# nvs_gps.net
KiCad netlist of a schematic drawn in EAGLE
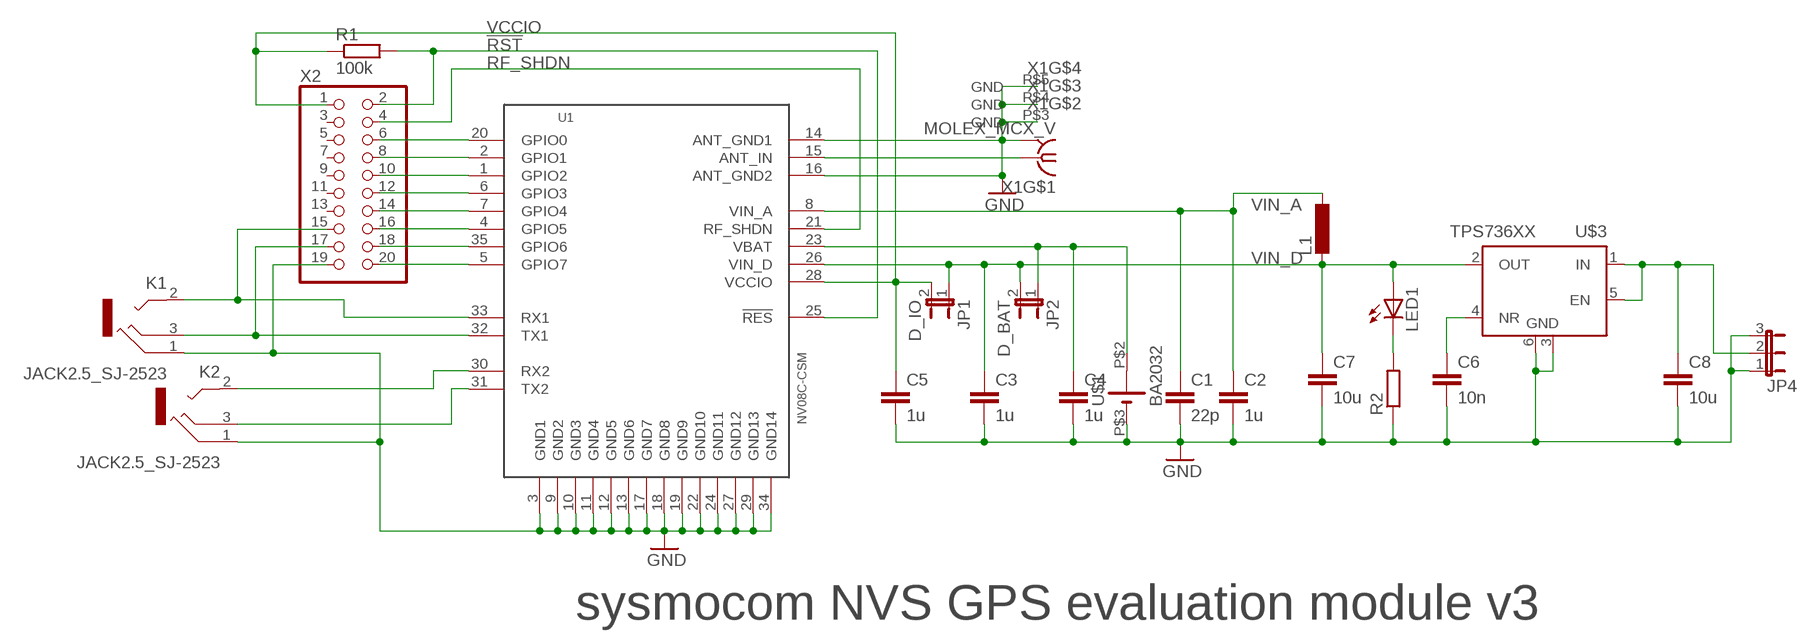
[diagram p0: schematic, sheet 1]

(export (version "E")
  (design (tool "Eeschema 10.0.6"))
  (components
    (comp (ref "C1")
      (value "22p")
      (footprint "eagle-import:C0402K")
      (libsource (lib "eagle-import") (part "C-EUC0402K"))
    )
    (comp (ref "C2")
      (value "1u")
      (footprint "eagle-import:C0603")
      (libsource (lib "eagle-import") (part "C-EUC0603"))
    )
    (comp (ref "C3")
      (value "1u")
      (footprint "eagle-import:C0603")
      (libsource (lib "eagle-import") (part "C-EUC0603"))
    )
    (comp (ref "C4")
      (value "1u")
      (footprint "eagle-import:C0603")
      (libsource (lib "eagle-import") (part "C-EUC0603"))
    )
    (comp (ref "C5")
      (value "1u")
      (footprint "eagle-import:C0603")
      (libsource (lib "eagle-import") (part "C-EUC0603"))
    )
    (comp (ref "C6")
      (value "10n")
      (footprint "eagle-import:C0603")
      (libsource (lib "eagle-import") (part "C-EUC0603"))
    )
    (comp (ref "C7")
      (value "10u")
      (footprint "eagle-import:C0603")
      (libsource (lib "eagle-import") (part "C-EUC0603"))
    )
    (comp (ref "C8")
      (value "10u")
      (footprint "eagle-import:C0603")
      (libsource (lib "eagle-import") (part "C-EUC0603"))
    )
    (comp (ref "JP1")
      (value "D_IO")
      (footprint "eagle-import:JP1")
      (libsource (lib "eagle-import") (part "JP1E"))
    )
    (comp (ref "JP2")
      (value "D_BAT")
      (footprint "eagle-import:JP1")
      (libsource (lib "eagle-import") (part "JP1E"))
    )
    (comp (ref "JP4")
      (value "JP2E")
      (footprint "eagle-import:JP2")
      (libsource (lib "eagle-import") (part "JP2E"))
    )
    (comp (ref "K1")
      (value "JACK2.5_SJ-2523")
      (footprint "eagle-import:JACK2.5_SJ-2523")
      (libsource (lib "eagle-import") (part "JACK2.5_SJ-2523"))
    )
    (comp (ref "K2")
      (value "JACK2.5_SJ-2523")
      (footprint "eagle-import:JACK2.5_SJ-2523")
      (libsource (lib "eagle-import") (part "JACK2.5_SJ-2523"))
    )
    (comp (ref "L1")
      (value "L-EU0603")
      (footprint "eagle-import:0603")
      (libsource (lib "eagle-import") (part "L-EU0603"))
    )
    (comp (ref "LED1")
      (value "LED0603")
      (footprint "eagle-import:LED-0603")
      (libsource (lib "eagle-import") (part "LED0603"))
    )
    (comp (ref "R1")
      (value "100k")
      (footprint "eagle-import:R0603")
      (libsource (lib "eagle-import") (part "R-EU_R0603"))
    )
    (comp (ref "R2")
      (value "R-EU_R0603")
      (footprint "eagle-import:R0603")
      (libsource (lib "eagle-import") (part "R-EU_R0603"))
    )
    (comp (ref "U$1")
      (value "BA2032")
      (footprint "eagle-import:BA2023-ND")
      (libsource (lib "eagle-import") (part "BA2032"))
    )
    (comp (ref "U$3")
      (value "TPS736XX")
      (footprint "eagle-import:SOT223-6")
      (libsource (lib "eagle-import") (part "TPS736XX"))
    )
    (comp (ref "U1")
      (value "NV08C-CSM")
      (footprint "eagle-import:NV08C-CSM")
      (libsource (lib "eagle-import") (part "NV08C-CSM"))
    )
    (comp (ref "X1")
      (value "MOLEX_MCX_V")
      (footprint "eagle-import:MOLEX_MCX_V")
      (libsource (lib "eagle-import") (part "MOLEX_MCX_V"))
    )
    (comp (ref "X2")
      (value "PINHD-2X10")
      (footprint "eagle-import:2X10")
      (libsource (lib "eagle-import") (part "PINHD-2X10"))
    )
  )
  (nets
    (net (code "1") (name "/RF_SHDN") (class "Default")
      (node (ref "U1") (pin "21") (pinfunction "RF_SHDN_21") (pintype "output"))
      (node (ref "X2") (pin "4") (pinfunction "4_4") (pintype "passive"))
    )
    (net (code "2") (name "/VCCIO") (class "Default")
      (node (ref "C5") (pin "1") (pinfunction "1_1") (pintype "passive"))
      (node (ref "JP1") (pin "2") (pinfunction "2_2") (pintype "passive"))
      (node (ref "R1") (pin "1") (pinfunction "1_1") (pintype "passive"))
      (node (ref "U1") (pin "28") (pinfunction "VCCIO_28") (pintype "power_in"))
      (node (ref "X2") (pin "1") (pinfunction "1_1") (pintype "passive"))
    )
    (net (code "3") (name "/VIN_A") (class "Default")
      (node (ref "C1") (pin "1") (pinfunction "1_1") (pintype "passive"))
      (node (ref "C2") (pin "1") (pinfunction "1_1") (pintype "passive"))
      (node (ref "L1") (pin "1") (pinfunction "1_1") (pintype "passive"))
      (node (ref "U1") (pin "8") (pinfunction "VIN_A_8") (pintype "power_in"))
    )
    (net (code "4") (name "/VIN_D") (class "Default")
      (node (ref "C3") (pin "1") (pinfunction "1_1") (pintype "passive"))
      (node (ref "C7") (pin "1") (pinfunction "1_1") (pintype "passive"))
      (node (ref "JP1") (pin "1") (pinfunction "1_1") (pintype "passive"))
      (node (ref "JP2") (pin "2") (pinfunction "2_2") (pintype "passive"))
      (node (ref "L1") (pin "2") (pinfunction "2_2") (pintype "passive"))
      (node (ref "LED1") (pin "A") (pinfunction "A_A") (pintype "passive"))
      (node (ref "U$3") (pin "2") (pinfunction "OUT_2") (pintype "passive"))
      (node (ref "U1") (pin "26") (pinfunction "VIN_D_26") (pintype "power_in"))
    )
    (net (code "5") (name "/~{RST}") (class "Default")
      (node (ref "R1") (pin "2") (pinfunction "2_2") (pintype "passive"))
      (node (ref "U1") (pin "25") (pinfunction "~{RES}_25") (pintype "input"))
      (node (ref "X2") (pin "2") (pinfunction "2_2") (pintype "passive"))
    )
    (net (code "6") (name "GND") (class "Default")
      (node (ref "C1") (pin "2") (pinfunction "2_2") (pintype "passive"))
      (node (ref "C2") (pin "2") (pinfunction "2_2") (pintype "passive"))
      (node (ref "C3") (pin "2") (pinfunction "2_2") (pintype "passive"))
      (node (ref "C4") (pin "2") (pinfunction "2_2") (pintype "passive"))
      (node (ref "C5") (pin "2") (pinfunction "2_2") (pintype "passive"))
      (node (ref "C6") (pin "2") (pinfunction "2_2") (pintype "passive"))
      (node (ref "C7") (pin "2") (pinfunction "2_2") (pintype "passive"))
      (node (ref "C8") (pin "2") (pinfunction "2_2") (pintype "passive"))
      (node (ref "JP4") (pin "1") (pinfunction "1_1") (pintype "passive"))
      (node (ref "JP4") (pin "3") (pinfunction "3_3") (pintype "passive"))
      (node (ref "K1") (pin "1") (pinfunction "RING_1") (pintype "passive"))
      (node (ref "K2") (pin "1") (pinfunction "RING_1") (pintype "passive"))
      (node (ref "R2") (pin "1") (pinfunction "1_1") (pintype "passive"))
      (node (ref "U$1") (pin "P$3") (pinfunction "-_P$3") (pintype "passive"))
      (node (ref "U$3") (pin "3") (pinfunction "GND_3") (pintype "power_in"))
      (node (ref "U$3") (pin "6") (pinfunction "GND1_6") (pintype "power_in"))
      (node (ref "U1") (pin "10") (pinfunction "GND3_10") (pintype "bidirectional"))
      (node (ref "U1") (pin "11") (pinfunction "GND4_11") (pintype "bidirectional"))
      (node (ref "U1") (pin "12") (pinfunction "GND5_12") (pintype "bidirectional"))
      (node (ref "U1") (pin "13") (pinfunction "GND6_13") (pintype "bidirectional"))
      (node (ref "U1") (pin "14") (pinfunction "ANT_GND1_14") (pintype "bidirectional"))
      (node (ref "U1") (pin "16") (pinfunction "ANT_GND2_16") (pintype "bidirectional"))
      (node (ref "U1") (pin "17") (pinfunction "GND7_17") (pintype "bidirectional"))
      (node (ref "U1") (pin "18") (pinfunction "GND8_18") (pintype "bidirectional"))
      (node (ref "U1") (pin "19") (pinfunction "GND9_19") (pintype "bidirectional"))
      (node (ref "U1") (pin "22") (pinfunction "GND10_22") (pintype "bidirectional"))
      (node (ref "U1") (pin "24") (pinfunction "GND11_24") (pintype "bidirectional"))
      (node (ref "U1") (pin "27") (pinfunction "GND12_27") (pintype "bidirectional"))
      (node (ref "U1") (pin "29") (pinfunction "GND13_29") (pintype "bidirectional"))
      (node (ref "U1") (pin "3") (pinfunction "GND1_3") (pintype "bidirectional"))
      (node (ref "U1") (pin "34") (pinfunction "GND14_34") (pintype "bidirectional"))
      (node (ref "U1") (pin "9") (pinfunction "GND2_9") (pintype "bidirectional"))
      (node (ref "X1") (pin "P$2") (pinfunction "GND_P$2") (pintype "power_in"))
      (node (ref "X1") (pin "P$3") (pinfunction "GND_P$3") (pintype "power_in"))
      (node (ref "X1") (pin "P$4") (pinfunction "GND_P$4") (pintype "power_in"))
      (node (ref "X1") (pin "P$5") (pinfunction "GND_P$5") (pintype "power_in"))
      (node (ref "X2") (pin "19") (pinfunction "19_19") (pintype "passive"))
    )
    (net (code "7") (name "Net-(K1-MIDDLE)") (class "Default")
      (node (ref "K1") (pin "3") (pinfunction "MIDDLE_3") (pintype "passive"))
      (node (ref "U1") (pin "32") (pinfunction "TX1_32") (pintype "output"))
      (node (ref "X2") (pin "17") (pinfunction "17_17") (pintype "passive"))
    )
    (net (code "8") (name "Net-(K1-TIP)") (class "Default")
      (node (ref "K1") (pin "2") (pinfunction "TIP_2") (pintype "passive"))
      (node (ref "U1") (pin "33") (pinfunction "RX1_33") (pintype "input"))
      (node (ref "X2") (pin "15") (pinfunction "15_15") (pintype "passive"))
    )
    (net (code "9") (name "Net-(K2-MIDDLE)") (class "Default")
      (node (ref "K2") (pin "3") (pinfunction "MIDDLE_3") (pintype "passive"))
      (node (ref "U1") (pin "31") (pinfunction "TX2_31") (pintype "output"))
    )
    (net (code "10") (name "Net-(K2-TIP)") (class "Default")
      (node (ref "K2") (pin "2") (pinfunction "TIP_2") (pintype "passive"))
      (node (ref "U1") (pin "30") (pinfunction "RX2_30") (pintype "input"))
    )
    (net (code "11") (name "Net-(LED1-PadC)") (class "Default")
      (node (ref "LED1") (pin "C") (pinfunction "C_C") (pintype "passive"))
      (node (ref "R2") (pin "2") (pinfunction "2_2") (pintype "passive"))
    )
    (net (code "12") (name "Net-(U$3-EN)") (class "Default")
      (node (ref "C8") (pin "1") (pinfunction "1_1") (pintype "passive"))
      (node (ref "JP4") (pin "2") (pinfunction "2_2") (pintype "passive"))
      (node (ref "U$3") (pin "1") (pinfunction "IN_1") (pintype "input"))
      (node (ref "U$3") (pin "5") (pinfunction "EN_5") (pintype "input"))
    )
    (net (code "13") (name "Net-(U$3-NR)") (class "Default")
      (node (ref "C6") (pin "1") (pinfunction "1_1") (pintype "passive"))
      (node (ref "U$3") (pin "4") (pinfunction "NR_4") (pintype "passive"))
    )
    (net (code "14") (name "Net-(U1-ANT_IN)") (class "Default")
      (node (ref "U1") (pin "15") (pinfunction "ANT_IN_15") (pintype "input"))
      (node (ref "X1") (pin "P$1") (pinfunction "1_P$1") (pintype "passive"))
    )
    (net (code "15") (name "Net-(U1-GPIO0)") (class "Default")
      (node (ref "U1") (pin "20") (pinfunction "GPIO0_20") (pintype "bidirectional"))
      (node (ref "X2") (pin "6") (pinfunction "6_6") (pintype "passive"))
    )
    (net (code "16") (name "Net-(U1-GPIO1)") (class "Default")
      (node (ref "U1") (pin "2") (pinfunction "GPIO1_2") (pintype "bidirectional"))
      (node (ref "X2") (pin "8") (pinfunction "8_8") (pintype "passive"))
    )
    (net (code "17") (name "Net-(U1-GPIO2)") (class "Default")
      (node (ref "U1") (pin "1") (pinfunction "GPIO2_1") (pintype "bidirectional"))
      (node (ref "X2") (pin "10") (pinfunction "10_10") (pintype "passive"))
    )
    (net (code "18") (name "Net-(U1-GPIO3)") (class "Default")
      (node (ref "U1") (pin "6") (pinfunction "GPIO3_6") (pintype "bidirectional"))
      (node (ref "X2") (pin "12") (pinfunction "12_12") (pintype "passive"))
    )
    (net (code "19") (name "Net-(U1-GPIO4)") (class "Default")
      (node (ref "U1") (pin "7") (pinfunction "GPIO4_7") (pintype "bidirectional"))
      (node (ref "X2") (pin "14") (pinfunction "14_14") (pintype "passive"))
    )
    (net (code "20") (name "Net-(U1-GPIO5)") (class "Default")
      (node (ref "U1") (pin "4") (pinfunction "GPIO5_4") (pintype "bidirectional"))
      (node (ref "X2") (pin "16") (pinfunction "16_16") (pintype "passive"))
    )
    (net (code "21") (name "Net-(U1-GPIO6)") (class "Default")
      (node (ref "U1") (pin "35") (pinfunction "GPIO6_35") (pintype "bidirectional"))
      (node (ref "X2") (pin "18") (pinfunction "18_18") (pintype "passive"))
    )
    (net (code "22") (name "Net-(U1-GPIO7)") (class "Default")
      (node (ref "U1") (pin "5") (pinfunction "GPIO7_5") (pintype "bidirectional"))
      (node (ref "X2") (pin "20") (pinfunction "20_20") (pintype "passive"))
    )
    (net (code "23") (name "Net-(U1-VBAT)") (class "Default")
      (node (ref "C4") (pin "1") (pinfunction "1_1") (pintype "passive"))
      (node (ref "JP2") (pin "1") (pinfunction "1_1") (pintype "passive"))
      (node (ref "U$1") (pin "P$2") (pinfunction "+_P$2") (pintype "passive"))
      (node (ref "U1") (pin "23") (pinfunction "VBAT_23") (pintype "input"))
    )
    (net (code "24") (name "unconnected-(U$1-+-PadP$1)") (class "Default")
      (node (ref "U$1") (pin "P$1") (pinfunction "+_P$1") (pintype "passive"))
    )
    (net (code "25") (name "unconnected-(X2-Pad3)") (class "Default")
      (node (ref "X2") (pin "3") (pinfunction "3_3") (pintype "passive"))
    )
    (net (code "26") (name "unconnected-(X2-Pad5)") (class "Default")
      (node (ref "X2") (pin "5") (pinfunction "5_5") (pintype "passive"))
    )
    (net (code "27") (name "unconnected-(X2-Pad7)") (class "Default")
      (node (ref "X2") (pin "7") (pinfunction "7_7") (pintype "passive"))
    )
    (net (code "28") (name "unconnected-(X2-Pad9)") (class "Default")
      (node (ref "X2") (pin "9") (pinfunction "9_9") (pintype "passive"))
    )
    (net (code "29") (name "unconnected-(X2-Pad11)") (class "Default")
      (node (ref "X2") (pin "11") (pinfunction "11_11") (pintype "passive"))
    )
    (net (code "30") (name "unconnected-(X2-Pad13)") (class "Default")
      (node (ref "X2") (pin "13") (pinfunction "13_13") (pintype "passive"))
    )
  )
)
